# project_buran_schematic.net
KiCad netlist of a schematic drawn in Altium Designer
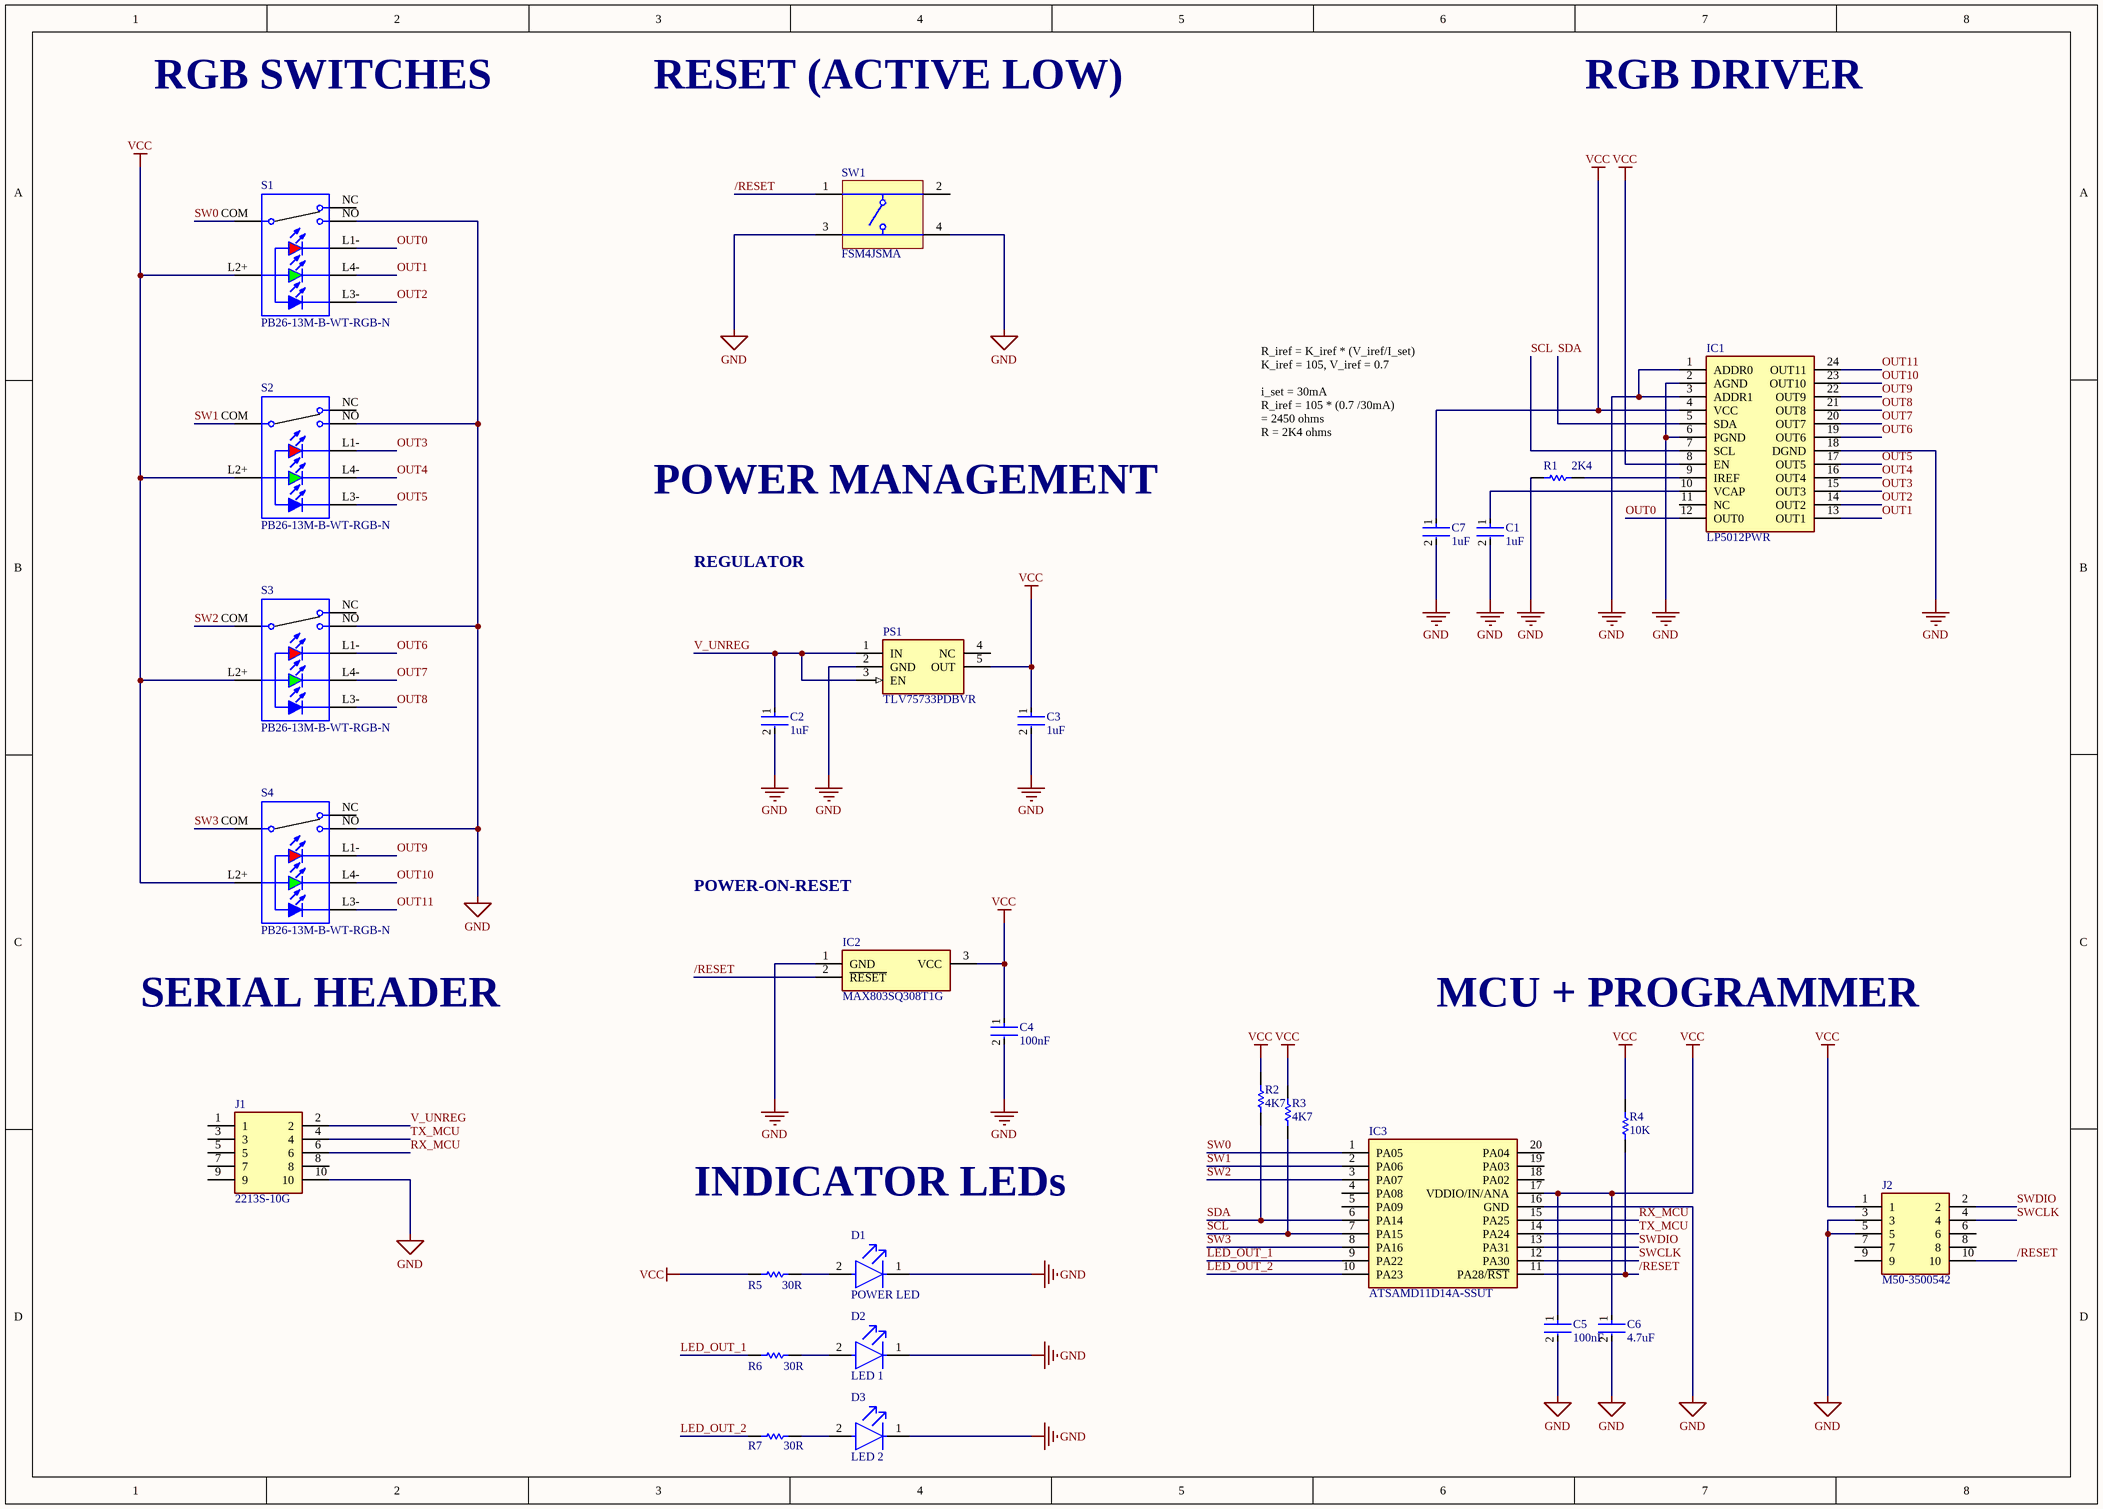
[diagram p0: project_buran_schematic.SchDoc]

(export (version "E")
  (design (tool "Eeschema 10.0.6"))
  (components
    (comp (ref "C1")
      (value "1uF")
      (footprint "FP-GRM188-0_1-e0_2_0_55-IPC_A")
      (description "Chip Multilayer Ceramic Capacitors for General Purpose, 0603, 10uF, X5R, 15%, 20%, 6.3V")
      (fields (field (name "VOLTAGE") "6.3V") (field (name "TOLERANCE") "20%"))
      (libsource (lib "Altium Content Vault") (part "02cd4be3c70576c341d710602a673aa"))
    )
    (comp (ref "C2")
      (value "1uF")
      (footprint "FP-GRM188-0_1-e0_2_0_55-IPC_A")
      (description "Chip Multilayer Ceramic Capacitors for General Purpose, 0603, 10uF, X5R, 15%, 20%, 6.3V")
      (fields (field (name "VOLTAGE") "6.3V") (field (name "TOLERANCE") "20%"))
      (libsource (lib "Altium Content Vault") (part "02cd4be3c70576c341d710602a673aa"))
    )
    (comp (ref "C3")
      (value "1uF")
      (footprint "FP-GRM188-0_1-e0_2_0_55-IPC_A")
      (description "Chip Multilayer Ceramic Capacitors for General Purpose, 0603, 10uF, X5R, 15%, 20%, 6.3V")
      (fields (field (name "VOLTAGE") "6.3V") (field (name "TOLERANCE") "20%"))
      (libsource (lib "Altium Content Vault") (part "02cd4be3c70576c341d710602a673aa"))
    )
    (comp (ref "C4")
      (value "100nF")
      (footprint "FP-GRM188-0_1-e0_2_0_55-IPC_A")
      (description "Chip Multilayer Ceramic Capacitors for General Purpose, 0603, 10uF, X5R, 15%, 20%, 6.3V")
      (fields (field (name "VOLTAGE") "6.3V") (field (name "TOLERANCE") "20%"))
      (libsource (lib "Altium Content Vault") (part "02cd4be3c70576c341d710602a673aa"))
    )
    (comp (ref "C5")
      (value "100nF")
      (footprint "FP-GRM188-0_1-e0_2_0_55-IPC_A")
      (description "Chip Multilayer Ceramic Capacitors for General Purpose, 0603, 10uF, X5R, 15%, 20%, 6.3V")
      (fields (field (name "VOLTAGE") "6.3V") (field (name "TOLERANCE") "20%"))
      (libsource (lib "Altium Content Vault") (part "02cd4be3c70576c341d710602a673aa"))
    )
    (comp (ref "C6")
      (value "4.7uF")
      (footprint "FP-GRM188-0_1-e0_2_0_55-IPC_A")
      (description "Chip Multilayer Ceramic Capacitors for General Purpose, 0603, 10uF, X5R, 15%, 20%, 6.3V")
      (fields (field (name "VOLTAGE") "6.3V") (field (name "TOLERANCE") "20%"))
      (libsource (lib "Altium Content Vault") (part "02cd4be3c70576c341d710602a673aa"))
    )
    (comp (ref "C7")
      (value "1uF")
      (footprint "FP-GRM188-0_1-e0_2_0_55-IPC_A")
      (description "Chip Multilayer Ceramic Capacitors for General Purpose, 0603, 10uF, X5R, 15%, 20%, 6.3V")
      (fields (field (name "VOLTAGE") "6.3V") (field (name "TOLERANCE") "20%"))
      (libsource (lib "Altium Content Vault") (part "02cd4be3c70576c341d710602a673aa"))
    )
    (comp (ref "D1")
      (value "POWER LED")
      (footprint "FP-LTST-C190GKT-MFG")
      (description "LED GREEN CLEAR CHIP SMD")
      (fields (field (name "VOLTAGE") "2V"))
      (libsource (lib "Altium Content Vault") (part "8706943c75ba83719d021d2fdc84c58"))
    )
    (comp (ref "D2")
      (value "LED 1")
      (footprint "FP-LTST-C190GKT-MFG")
      (description "LED GREEN CLEAR CHIP SMD")
      (fields (field (name "VOLTAGE") "2V"))
      (libsource (lib "Altium Content Vault") (part "8706943c75ba83719d021d2fdc84c58"))
    )
    (comp (ref "D3")
      (value "LED 2")
      (footprint "FP-LTST-C190GKT-MFG")
      (description "LED GREEN CLEAR CHIP SMD")
      (fields (field (name "VOLTAGE") "2V"))
      (libsource (lib "Altium Content Vault") (part "8706943c75ba83719d021d2fdc84c58"))
    )
    (comp (ref "IC1")
      (value "LP5012PWR")
      (footprint "SOP65P640X120-24N")
      (description "Integrated Circuit")
      (fields (field (name "MOUSER PART NUMBER") "595-LP5012PWR"))
      (libsource (lib "*") (part "LP5012PWR"))
    )
    (comp (ref "IC2")
      (value "MAX803SQ308T1G")
      (footprint "SamacSys:SOT65P220X100-3N")
      (description "Integrated Circuit")
      (fields (field (name "MOUSER PART NUMBER") "863-MAX803SQ308T1G"))
      (libsource (lib "*") (part "MAX803SQ308T1G"))
    )
    (comp (ref "IC3")
      (value "ATSAMD11D14A-SSUT")
      (footprint "SamacSys:SOIC127P1032X265-20N")
      (description "Integrated Circuit")
      (fields (field (name "MOUSER PART NUMBER") "556-ATSAMD11D14ASSUT"))
      (libsource (lib "*") (part "ATSAMD11D14A-SSUT"))
    )
    (comp (ref "J1")
      (value "2213S-10G")
      (footprint "SamacSys:HDRV10W64P254_2X5_1270X508X854P")
      (description "Connector")
      (libsource (lib "*") (part "2213S-10G"))
    )
    (comp (ref "J2")
      (value "M50-3500542")
      (footprint "SamacSys:M503500542")
      (description "Connector")
      (fields (field (name "MOUSER PART NUMBER") "855-M50-3500542"))
      (libsource (lib "SamacSys") (part "M50-3500542"))
    )
    (comp (ref "PS1")
      (value "TLV75733PDBVR")
      (footprint "SamacSys:SOT95P280X145-5N")
      (description "Power Supply")
      (fields (field (name "MOUSER PART NUMBER") "595-TLV75733PDBVR"))
      (libsource (lib "SamacSys") (part "TLV75733PDBVR"))
    )
    (comp (ref "R1")
      (value "2K4")
      (footprint "RESC1609X50X30NL10T20")
      (fields (field (name "PART NUMBER") "CRCW0603110RFKEA") (field (name "MANUFACTURER") "Vishay Dale"))
      (libsource (lib "Altium Content Vault") (part "RES"))
    )
    (comp (ref "R2")
      (value "4K7")
      (footprint "RESC1609X50X30NL10T20")
      (fields (field (name "PART NUMBER") "CRCW0603110RFKEA") (field (name "MANUFACTURER") "Vishay Dale"))
      (libsource (lib "Altium Content Vault") (part "RES"))
    )
    (comp (ref "R3")
      (value "4K7")
      (footprint "RESC1609X50X30NL10T20")
      (fields (field (name "PART NUMBER") "CRCW0603110RFKEA") (field (name "MANUFACTURER") "Vishay Dale"))
      (libsource (lib "Altium Content Vault") (part "RES"))
    )
    (comp (ref "R4")
      (value "10K")
      (footprint "RESC1609X50X30NL10T20")
      (fields (field (name "PART NUMBER") "CRCW0603110RFKEA") (field (name "MANUFACTURER") "Vishay Dale"))
      (libsource (lib "Altium Content Vault") (part "RES"))
    )
    (comp (ref "R5")
      (value "30R")
      (footprint "RESC1609X50X30NL10T20")
      (fields (field (name "PART NUMBER") "CRCW0603110RFKEA") (field (name "MANUFACTURER") "Vishay Dale"))
      (libsource (lib "Altium Content Vault") (part "RES"))
    )
    (comp (ref "R6")
      (value "30R")
      (footprint "RESC1609X50X30NL10T20")
      (fields (field (name "PART NUMBER") "CRCW0603110RFKEA") (field (name "MANUFACTURER") "Vishay Dale"))
      (libsource (lib "Altium Content Vault") (part "RES"))
    )
    (comp (ref "R7")
      (value "30R")
      (footprint "RESC1609X50X30NL10T20")
      (fields (field (name "PART NUMBER") "CRCW0603110RFKEA") (field (name "MANUFACTURER") "Vishay Dale"))
      (libsource (lib "Altium Content Vault") (part "RES"))
    )
    (comp (ref "S1")
      (value "PB26-13M-B-WT-RGB-N")
      (footprint "RGB Switch")
      (description "WS-PBTL Illuminated THT Push Button Switch, Red & Green & Blue")
      (fields (field (name "PART NUMBER") "465M111172501") (field (name "PUBLISHER") "Wurth Elektronik"))
      (libsource (lib "BuranComponent") (part "PB26-13M-B-WT-RGB-N"))
    )
    (comp (ref "S2")
      (value "PB26-13M-B-WT-RGB-N")
      (footprint "RGB Switch")
      (description "WS-PBTL Illuminated THT Push Button Switch, Red & Green & Blue")
      (fields (field (name "PART NUMBER") "465M111172501") (field (name "PUBLISHER") "Wurth Elektronik"))
      (libsource (lib "BuranComponent") (part "PB26-13M-B-WT-RGB-N"))
    )
    (comp (ref "S3")
      (value "PB26-13M-B-WT-RGB-N")
      (footprint "RGB Switch")
      (description "WS-PBTL Illuminated THT Push Button Switch, Red & Green & Blue")
      (fields (field (name "PART NUMBER") "465M111172501") (field (name "PUBLISHER") "Wurth Elektronik"))
      (libsource (lib "BuranComponent") (part "PB26-13M-B-WT-RGB-N"))
    )
    (comp (ref "S4")
      (value "PB26-13M-B-WT-RGB-N")
      (footprint "RGB Switch")
      (description "WS-PBTL Illuminated THT Push Button Switch, Red & Green & Blue")
      (fields (field (name "PART NUMBER") "465M111172501") (field (name "PUBLISHER") "Wurth Elektronik"))
      (libsource (lib "BuranComponent") (part "PB26-13M-B-WT-RGB-N"))
    )
    (comp (ref "SW1")
      (value "FSM4JSMA")
      (footprint "TECO-FSM4JSMA_V")
      (description "Swicth, SPST, 24 V, -35 to 85 degC, 4-Pin SMD, RoHS, Tape and Reel")
      (fields (field (name "MANUFACTURER") "TE Connectivity"))
      (libsource (lib "Altium Content Vault") (part "SW-SPST-4_A"))
    )
  )
  (nets
    (net (code "1") (name "/LED_OUT_1") (class "Default")
      (node (ref "IC3") (pin "9") (pinfunction "PA22_9") (pintype "passive"))
      (node (ref "R6") (pin "2") (pinfunction "2_2") (pintype "passive"))
    )
    (net (code "2") (name "/LED_OUT_2") (class "Default")
      (node (ref "IC3") (pin "10") (pinfunction "PA23_10") (pintype "passive"))
      (node (ref "R7") (pin "2") (pinfunction "2_2") (pintype "passive"))
    )
    (net (code "3") (name "/OUT0") (class "Default")
      (node (ref "IC1") (pin "12") (pinfunction "OUT0_12") (pintype "passive"))
      (node (ref "S1") (pin "L1-") (pinfunction "L1-_L1-") (pintype "passive"))
    )
    (net (code "4") (name "/OUT1") (class "Default")
      (node (ref "IC1") (pin "13") (pinfunction "OUT1_13") (pintype "passive"))
      (node (ref "S1") (pin "L4-") (pinfunction "L2_L4-") (pintype "passive"))
    )
    (net (code "5") (name "/OUT2") (class "Default")
      (node (ref "IC1") (pin "14") (pinfunction "OUT2_14") (pintype "passive"))
      (node (ref "S1") (pin "L3-") (pinfunction "L3-_L3-") (pintype "passive"))
    )
    (net (code "6") (name "/OUT3") (class "Default")
      (node (ref "IC1") (pin "15") (pinfunction "OUT3_15") (pintype "passive"))
      (node (ref "S2") (pin "L1-") (pinfunction "L1-_L1-") (pintype "passive"))
    )
    (net (code "7") (name "/OUT4") (class "Default")
      (node (ref "IC1") (pin "16") (pinfunction "OUT4_16") (pintype "passive"))
      (node (ref "S2") (pin "L4-") (pinfunction "L2_L4-") (pintype "passive"))
    )
    (net (code "8") (name "/OUT5") (class "Default")
      (node (ref "IC1") (pin "17") (pinfunction "OUT5_17") (pintype "passive"))
      (node (ref "S2") (pin "L3-") (pinfunction "L3-_L3-") (pintype "passive"))
    )
    (net (code "9") (name "/OUT6") (class "Default")
      (node (ref "IC1") (pin "19") (pinfunction "OUT6_19") (pintype "passive"))
      (node (ref "S3") (pin "L1-") (pinfunction "L1-_L1-") (pintype "passive"))
    )
    (net (code "10") (name "/OUT7") (class "Default")
      (node (ref "IC1") (pin "20") (pinfunction "OUT7_20") (pintype "passive"))
      (node (ref "S3") (pin "L4-") (pinfunction "L2_L4-") (pintype "passive"))
    )
    (net (code "11") (name "/OUT8") (class "Default")
      (node (ref "IC1") (pin "21") (pinfunction "OUT8_21") (pintype "passive"))
      (node (ref "S3") (pin "L3-") (pinfunction "L3-_L3-") (pintype "passive"))
    )
    (net (code "12") (name "/OUT9") (class "Default")
      (node (ref "IC1") (pin "22") (pinfunction "OUT9_22") (pintype "passive"))
      (node (ref "S4") (pin "L1-") (pinfunction "L1-_L1-") (pintype "passive"))
    )
    (net (code "13") (name "/OUT10") (class "Default")
      (node (ref "IC1") (pin "23") (pinfunction "OUT10_23") (pintype "passive"))
      (node (ref "S4") (pin "L4-") (pinfunction "L2_L4-") (pintype "passive"))
    )
    (net (code "14") (name "/OUT11") (class "Default")
      (node (ref "IC1") (pin "24") (pinfunction "OUT11_24") (pintype "passive"))
      (node (ref "S4") (pin "L3-") (pinfunction "L3-_L3-") (pintype "passive"))
    )
    (net (code "15") (name "/RX_MCU") (class "Default")
      (node (ref "IC3") (pin "15") (pinfunction "PA25_15") (pintype "passive"))
      (node (ref "J1") (pin "6") (pinfunction "6_6") (pintype "passive"))
    )
    (net (code "16") (name "/SCL") (class "Default")
      (node (ref "IC1") (pin "7") (pinfunction "SCL_7") (pintype "passive"))
      (node (ref "IC3") (pin "7") (pinfunction "PA15_7") (pintype "passive"))
      (node (ref "R3") (pin "1") (pinfunction "1_1") (pintype "passive"))
    )
    (net (code "17") (name "/SDA") (class "Default")
      (node (ref "IC1") (pin "5") (pinfunction "SDA_5") (pintype "passive"))
      (node (ref "IC3") (pin "6") (pinfunction "PA14_6") (pintype "passive"))
      (node (ref "R2") (pin "1") (pinfunction "1_1") (pintype "passive"))
    )
    (net (code "18") (name "/SW0") (class "Default")
      (node (ref "IC3") (pin "1") (pinfunction "PA05_1") (pintype "passive"))
      (node (ref "S1") (pin "COM") (pinfunction "COM_COM") (pintype "passive"))
    )
    (net (code "19") (name "/SW1") (class "Default")
      (node (ref "IC3") (pin "2") (pinfunction "PA06_2") (pintype "passive"))
      (node (ref "S2") (pin "COM") (pinfunction "COM_COM") (pintype "passive"))
    )
    (net (code "20") (name "/SW2") (class "Default")
      (node (ref "IC3") (pin "3") (pinfunction "PA07_3") (pintype "passive"))
      (node (ref "S3") (pin "COM") (pinfunction "COM_COM") (pintype "passive"))
    )
    (net (code "21") (name "/SW3") (class "Default")
      (node (ref "IC3") (pin "8") (pinfunction "PA16_8") (pintype "passive"))
      (node (ref "S4") (pin "COM") (pinfunction "COM_COM") (pintype "passive"))
    )
    (net (code "22") (name "/SWCLK") (class "Default")
      (node (ref "IC3") (pin "12") (pinfunction "PA30_12") (pintype "passive"))
      (node (ref "J2") (pin "4") (pinfunction "4_4") (pintype "passive"))
    )
    (net (code "23") (name "/SWDIO") (class "Default")
      (node (ref "IC3") (pin "13") (pinfunction "PA31_13") (pintype "passive"))
      (node (ref "J2") (pin "2") (pinfunction "2_2") (pintype "passive"))
    )
    (net (code "24") (name "/TX_MCU") (class "Default")
      (node (ref "IC3") (pin "14") (pinfunction "PA24_14") (pintype "passive"))
      (node (ref "J1") (pin "4") (pinfunction "4_4") (pintype "passive"))
    )
    (net (code "25") (name "/V_UNREG") (class "Default")
      (node (ref "C2") (pin "1") (pinfunction "1_1") (pintype "passive"))
      (node (ref "J1") (pin "2") (pinfunction "2_2") (pintype "passive"))
      (node (ref "PS1") (pin "1") (pinfunction "IN_1") (pintype "power_in"))
      (node (ref "PS1") (pin "3") (pinfunction "EN_3") (pintype "input"))
    )
    (net (code "26") (name "/{slash}RESET") (class "Default")
      (node (ref "IC2") (pin "2") (pinfunction "~{RESET}_2") (pintype "passive"))
      (node (ref "IC3") (pin "11") (pinfunction "PA28/~{RST}_11") (pintype "passive"))
      (node (ref "J2") (pin "10") (pinfunction "10_10") (pintype "passive"))
      (node (ref "R4") (pin "1") (pinfunction "1_1") (pintype "passive"))
      (node (ref "SW1") (pin "1") (pinfunction "1_1") (pintype "passive"))
    )
    (net (code "27") (name "GND") (class "Default")
      (node (ref "C1") (pin "2") (pinfunction "2_2") (pintype "passive"))
      (node (ref "C2") (pin "2") (pinfunction "2_2") (pintype "passive"))
      (node (ref "C3") (pin "2") (pinfunction "2_2") (pintype "passive"))
      (node (ref "C4") (pin "2") (pinfunction "2_2") (pintype "passive"))
      (node (ref "C5") (pin "2") (pinfunction "2_2") (pintype "passive"))
      (node (ref "C6") (pin "2") (pinfunction "2_2") (pintype "passive"))
      (node (ref "C7") (pin "2") (pinfunction "2_2") (pintype "passive"))
      (node (ref "D1") (pin "1") (pinfunction "C_1") (pintype "passive"))
      (node (ref "D2") (pin "1") (pinfunction "C_1") (pintype "passive"))
      (node (ref "D3") (pin "1") (pinfunction "C_1") (pintype "passive"))
      (node (ref "IC1") (pin "1") (pinfunction "ADDR0_1") (pintype "passive"))
      (node (ref "IC1") (pin "18") (pinfunction "DGND_18") (pintype "passive"))
      (node (ref "IC1") (pin "2") (pinfunction "AGND_2") (pintype "passive"))
      (node (ref "IC1") (pin "3") (pinfunction "ADDR1_3") (pintype "passive"))
      (node (ref "IC1") (pin "6") (pinfunction "PGND_6") (pintype "passive"))
      (node (ref "IC2") (pin "1") (pinfunction "GND_1") (pintype "power_in"))
      (node (ref "IC3") (pin "16") (pinfunction "GND_16") (pintype "passive"))
      (node (ref "J1") (pin "10") (pinfunction "10_10") (pintype "passive"))
      (node (ref "J2") (pin "3") (pinfunction "3_3") (pintype "passive"))
      (node (ref "J2") (pin "5") (pinfunction "5_5") (pintype "passive"))
      (node (ref "PS1") (pin "2") (pinfunction "GND_2") (pintype "power_in"))
      (node (ref "R1") (pin "1") (pinfunction "1_1") (pintype "passive"))
      (node (ref "S1") (pin "NO") (pinfunction "NO_NO") (pintype "passive"))
      (node (ref "S2") (pin "NO") (pinfunction "NO_NO") (pintype "passive"))
      (node (ref "S3") (pin "NO") (pinfunction "NO_NO") (pintype "passive"))
      (node (ref "S4") (pin "NO") (pinfunction "NO_NO") (pintype "passive"))
      (node (ref "SW1") (pin "3") (pinfunction "3_3") (pintype "passive"))
      (node (ref "SW1") (pin "4") (pinfunction "4_4") (pintype "passive"))
    )
    (net (code "28") (name "Net-(D1-A)") (class "Default")
      (node (ref "D1") (pin "2") (pinfunction "A_2") (pintype "passive"))
      (node (ref "R5") (pin "1") (pinfunction "1_1") (pintype "passive"))
    )
    (net (code "29") (name "Net-(D2-A)") (class "Default")
      (node (ref "D2") (pin "2") (pinfunction "A_2") (pintype "passive"))
      (node (ref "R6") (pin "1") (pinfunction "1_1") (pintype "passive"))
    )
    (net (code "30") (name "Net-(D3-A)") (class "Default")
      (node (ref "D3") (pin "2") (pinfunction "A_2") (pintype "passive"))
      (node (ref "R7") (pin "1") (pinfunction "1_1") (pintype "passive"))
    )
    (net (code "31") (name "Net-(IC1-IREF)") (class "Default")
      (node (ref "IC1") (pin "9") (pinfunction "IREF_9") (pintype "passive"))
      (node (ref "R1") (pin "2") (pinfunction "2_2") (pintype "passive"))
    )
    (net (code "32") (name "Net-(IC1-VCAP)") (class "Default")
      (node (ref "C1") (pin "1") (pinfunction "1_1") (pintype "passive"))
      (node (ref "IC1") (pin "10") (pinfunction "VCAP_10") (pintype "passive"))
    )
    (net (code "33") (name "VCC") (class "Default")
      (node (ref "C3") (pin "1") (pinfunction "1_1") (pintype "passive"))
      (node (ref "C4") (pin "1") (pinfunction "1_1") (pintype "passive"))
      (node (ref "C5") (pin "1") (pinfunction "1_1") (pintype "passive"))
      (node (ref "C6") (pin "1") (pinfunction "1_1") (pintype "passive"))
      (node (ref "C7") (pin "1") (pinfunction "1_1") (pintype "passive"))
      (node (ref "IC1") (pin "4") (pinfunction "VCC_4") (pintype "passive"))
      (node (ref "IC1") (pin "8") (pinfunction "EN_8") (pintype "passive"))
      (node (ref "IC2") (pin "3") (pinfunction "VCC_3") (pintype "power_in"))
      (node (ref "IC3") (pin "17") (pinfunction "VDDIO/IN/ANA_17") (pintype "passive"))
      (node (ref "J2") (pin "1") (pinfunction "1_1") (pintype "passive"))
      (node (ref "PS1") (pin "5") (pinfunction "OUT_5") (pintype "power_in"))
      (node (ref "R2") (pin "2") (pinfunction "2_2") (pintype "passive"))
      (node (ref "R3") (pin "2") (pinfunction "2_2") (pintype "passive"))
      (node (ref "R4") (pin "2") (pinfunction "2_2") (pintype "passive"))
      (node (ref "R5") (pin "2") (pinfunction "2_2") (pintype "passive"))
      (node (ref "S1") (pin "L2+") (pinfunction "L2+_L2+") (pintype "passive"))
      (node (ref "S2") (pin "L2+") (pinfunction "L2+_L2+") (pintype "passive"))
      (node (ref "S3") (pin "L2+") (pinfunction "L2+_L2+") (pintype "passive"))
      (node (ref "S4") (pin "L2+") (pinfunction "L2+_L2+") (pintype "passive"))
    )
    (net (code "34") (name "unconnected-(IC1-NC-Pad11)") (class "Default")
      (node (ref "IC1") (pin "11") (pinfunction "NC_11") (pintype "passive"))
    )
    (net (code "35") (name "unconnected-(IC3-PA02-Pad18)") (class "Default")
      (node (ref "IC3") (pin "18") (pinfunction "PA02_18") (pintype "passive"))
    )
    (net (code "36") (name "unconnected-(IC3-PA03-Pad19)") (class "Default")
      (node (ref "IC3") (pin "19") (pinfunction "PA03_19") (pintype "passive"))
    )
    (net (code "37") (name "unconnected-(IC3-PA04-Pad20)") (class "Default")
      (node (ref "IC3") (pin "20") (pinfunction "PA04_20") (pintype "passive"))
    )
    (net (code "38") (name "unconnected-(IC3-PA08-Pad4)") (class "Default")
      (node (ref "IC3") (pin "4") (pinfunction "PA08_4") (pintype "passive"))
    )
    (net (code "39") (name "unconnected-(IC3-PA09-Pad5)") (class "Default")
      (node (ref "IC3") (pin "5") (pinfunction "PA09_5") (pintype "passive"))
    )
    (net (code "40") (name "unconnected-(J1-Pad1)") (class "Default")
      (node (ref "J1") (pin "1") (pinfunction "1_1") (pintype "passive"))
    )
    (net (code "41") (name "unconnected-(J1-Pad3)") (class "Default")
      (node (ref "J1") (pin "3") (pinfunction "3_3") (pintype "passive"))
    )
    (net (code "42") (name "unconnected-(J1-Pad5)") (class "Default")
      (node (ref "J1") (pin "5") (pinfunction "5_5") (pintype "passive"))
    )
    (net (code "43") (name "unconnected-(J1-Pad7)") (class "Default")
      (node (ref "J1") (pin "7") (pinfunction "7_7") (pintype "passive"))
    )
    (net (code "44") (name "unconnected-(J1-Pad8)") (class "Default")
      (node (ref "J1") (pin "8") (pinfunction "8_8") (pintype "passive"))
    )
    (net (code "45") (name "unconnected-(J1-Pad9)") (class "Default")
      (node (ref "J1") (pin "9") (pinfunction "9_9") (pintype "passive"))
    )
    (net (code "46") (name "unconnected-(J2-Pad6)") (class "Default")
      (node (ref "J2") (pin "6") (pinfunction "6_6") (pintype "passive"))
    )
    (net (code "47") (name "unconnected-(J2-Pad7)") (class "Default")
      (node (ref "J2") (pin "7") (pinfunction "7_7") (pintype "passive"))
    )
    (net (code "48") (name "unconnected-(J2-Pad8)") (class "Default")
      (node (ref "J2") (pin "8") (pinfunction "8_8") (pintype "passive"))
    )
    (net (code "49") (name "unconnected-(J2-Pad9)") (class "Default")
      (node (ref "J2") (pin "9") (pinfunction "9_9") (pintype "passive"))
    )
    (net (code "50") (name "unconnected-(PS1-NC-Pad4)") (class "Default")
      (node (ref "PS1") (pin "4") (pinfunction "NC_4") (pintype "passive"))
    )
    (net (code "51") (name "unconnected-(S1-PadNC)") (class "Default")
      (node (ref "S1") (pin "NC") (pinfunction "NC_NC") (pintype "passive"))
    )
    (net (code "52") (name "unconnected-(S2-PadNC)") (class "Default")
      (node (ref "S2") (pin "NC") (pinfunction "NC_NC") (pintype "passive"))
    )
    (net (code "53") (name "unconnected-(S3-PadNC)") (class "Default")
      (node (ref "S3") (pin "NC") (pinfunction "NC_NC") (pintype "passive"))
    )
    (net (code "54") (name "unconnected-(S4-PadNC)") (class "Default")
      (node (ref "S4") (pin "NC") (pinfunction "NC_NC") (pintype "passive"))
    )
    (net (code "55") (name "unconnected-(SW1-Pad2)") (class "Default")
      (node (ref "SW1") (pin "2") (pinfunction "2_2") (pintype "passive"))
    )
  )
)
